# Sheet1.net
KiCad netlist of a schematic drawn in Altium Designer
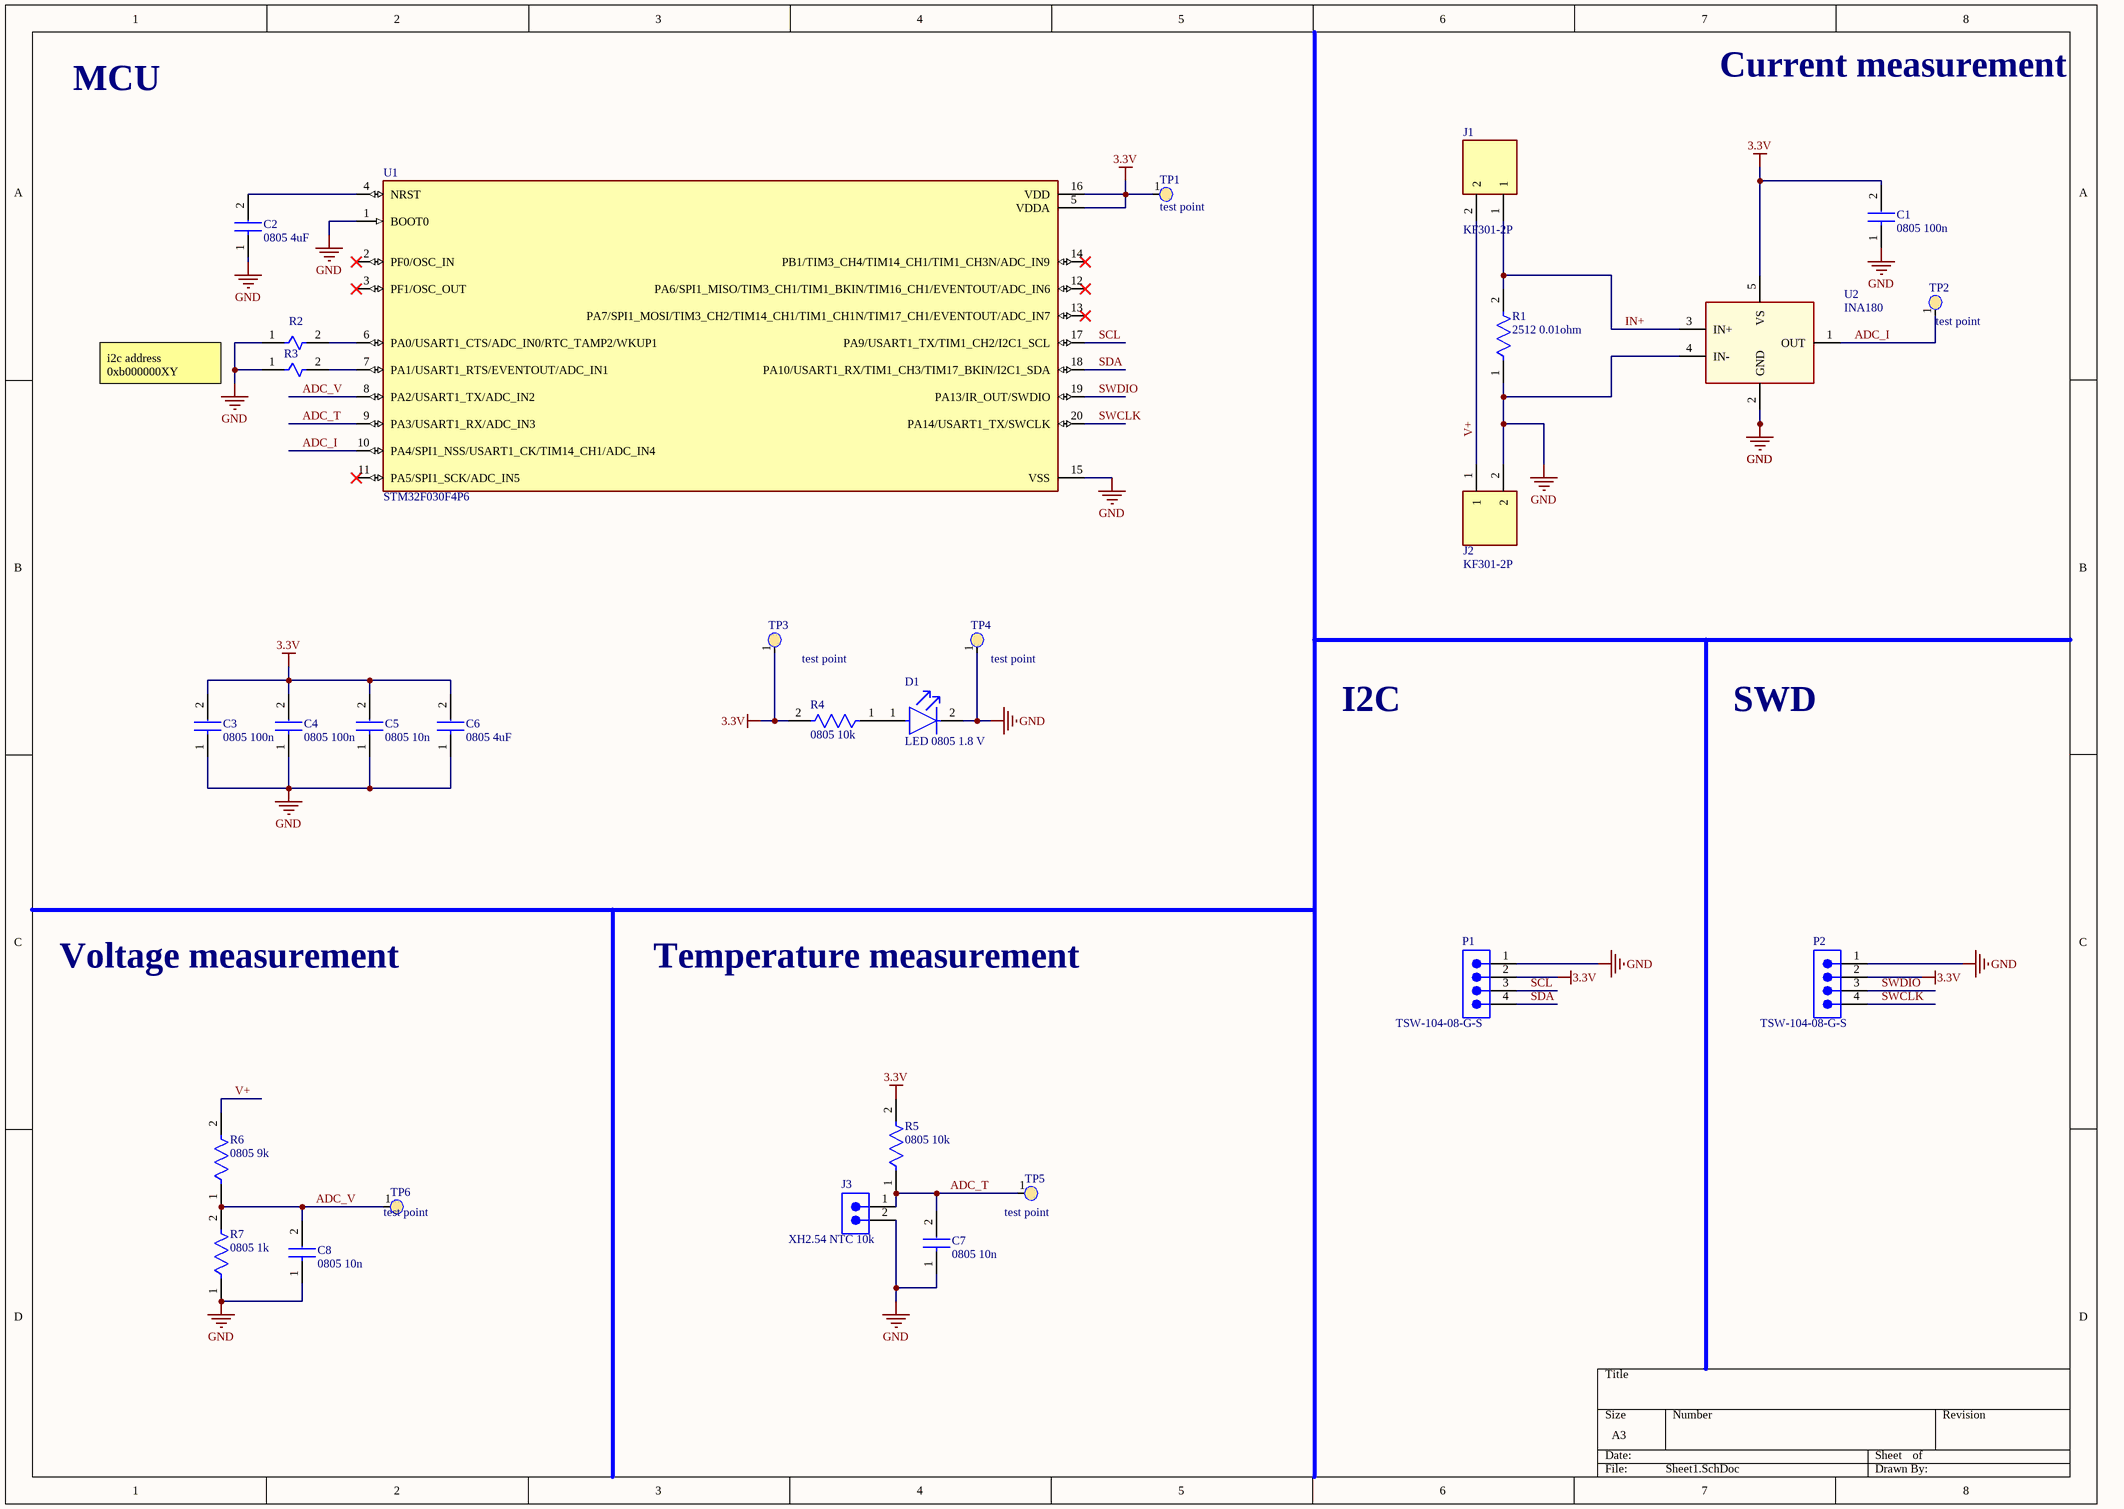
[diagram p0: Sheet1.SchDoc]

(export (version "E")
  (design (tool "Eeschema 10.0.6"))
  (components
    (comp (ref "C1")
      (value "0805 100n")
      (footprint "CAP 0805 IPC_A")
      (description "Chip Multilayer Ceramic Capacitors for General Purpose, 0805, 2200pF, C0G, 30ppm/°C, 5%, 250V")
      (fields (field (name "TOLERANCE") "5%"))
      (libsource (lib "Schlib1") (part "CAP"))
    )
    (comp (ref "C2")
      (value "0805 4uF")
      (footprint "CAP 0805 IPC_A")
      (description "Chip Multilayer Ceramic Capacitors for General Purpose, 0805, 2200pF, C0G, 30ppm/°C, 5%, 250V")
      (fields (field (name "TOLERANCE") "5%"))
      (libsource (lib "Schlib1") (part "CAP"))
    )
    (comp (ref "C3")
      (value "0805 100n")
      (footprint "CAP 0805 IPC_A")
      (description "Chip Multilayer Ceramic Capacitors for General Purpose, 0805, 2200pF, C0G, 30ppm/°C, 5%, 250V")
      (fields (field (name "TOLERANCE") "5%"))
      (libsource (lib "Schlib1") (part "CAP"))
    )
    (comp (ref "C4")
      (value "0805 100n")
      (footprint "CAP 0805 IPC_A")
      (description "Chip Multilayer Ceramic Capacitors for General Purpose, 0805, 2200pF, C0G, 30ppm/°C, 5%, 250V")
      (fields (field (name "TOLERANCE") "5%"))
      (libsource (lib "Schlib1") (part "CAP"))
    )
    (comp (ref "C5")
      (value "0805 10n")
      (footprint "CAP 0805 IPC_A")
      (description "Chip Multilayer Ceramic Capacitors for General Purpose, 0805, 2200pF, C0G, 30ppm/°C, 5%, 250V")
      (fields (field (name "TOLERANCE") "5%"))
      (libsource (lib "Schlib1") (part "CAP"))
    )
    (comp (ref "C6")
      (value "0805 4uF")
      (footprint "CAP 0805 IPC_A")
      (description "Chip Multilayer Ceramic Capacitors for General Purpose, 0805, 2200pF, C0G, 30ppm/°C, 5%, 250V")
      (fields (field (name "TOLERANCE") "5%"))
      (libsource (lib "Schlib1") (part "CAP"))
    )
    (comp (ref "C7")
      (value "0805 10n")
      (footprint "CAP 0805 IPC_A")
      (description "Chip Multilayer Ceramic Capacitors for General Purpose, 0805, 2200pF, C0G, 30ppm/°C, 5%, 250V")
      (fields (field (name "TOLERANCE") "5%"))
      (libsource (lib "Schlib1") (part "CAP"))
    )
    (comp (ref "C8")
      (value "0805 10n")
      (footprint "CAP 0805 IPC_A")
      (description "Chip Multilayer Ceramic Capacitors for General Purpose, 0805, 2200pF, C0G, 30ppm/°C, 5%, 250V")
      (fields (field (name "TOLERANCE") "5%"))
      (libsource (lib "Schlib1") (part "CAP"))
    )
    (comp (ref "D1")
      (value "LED 0805 1.8 V")
      (footprint "LED-0805- MFG")
      (description "LED BLUE CLEAR 0805 SMD")
      (libsource (lib "Schlib1") (part "led 0805"))
    )
    (comp (ref "J1")
      (value "KF301-2P")
      (footprint "KF301")
      (description "2 Pin Terminal Block 5mm Pitch")
      (fields (field (name "MF") "Handson Technology"))
      (libsource (lib "") (part "KF301-2P_1"))
    )
    (comp (ref "J2")
      (value "KF301-2P")
      (footprint "KF301")
      (description "2 Pin Terminal Block 5mm Pitch")
      (fields (field (name "MF") "Handson Technology"))
      (libsource (lib "Schlib1") (part "KF301-2P"))
    )
    (comp (ref "J3")
      (value "XH2.54 NTC 10k")
      (footprint "B2B-XH-A_LF_SN-MFG")
      (description "CONN HEADER VERT 2POS 2.5MM")
      (libsource (lib "Schlib1") (part "XH2.54 2 pin"))
    )
    (comp (ref "P1")
      (value "TSW-104-08-G-S")
      (footprint "header4pin")
      (description "0.025\" SQ Post Header, Through-hole, Vertical, -55 to 125 degC, 2.54 mm Pitch, 4-Pin, Male, RoHS")
      (fields (field (name "MANUFACTURER") "Samtec"))
      (libsource (lib "Schlib1") (part "header4pin"))
    )
    (comp (ref "P2")
      (value "TSW-104-08-G-S")
      (footprint "header4pin")
      (description "0.025\" SQ Post Header, Through-hole, Vertical, -55 to 125 degC, 2.54 mm Pitch, 4-Pin, Male, RoHS")
      (fields (field (name "MANUFACTURER") "Samtec"))
      (libsource (lib "Schlib1") (part "header4pin"))
    )
    (comp (ref "R1")
      (value "2512 0.01ohm")
      (footprint "R 2512 A")
      (libsource (lib "Schlib1") (part "R 2512"))
    )
    (comp (ref "R2") (value "0603") (footprint "0603-IPC_C") (libsource (lib "Schlib1") (part "0603")))
    (comp (ref "R3") (value "0603") (footprint "0603-IPC_C") (libsource (lib "Schlib1") (part "0603")))
    (comp (ref "R4") (value "0805 10k") (footprint "R 0805 A") (libsource (lib "Schlib1") (part "R 0805")))
    (comp (ref "R5") (value "0805 10k") (footprint "R 0805 A") (libsource (lib "Schlib1") (part "R 0805")))
    (comp (ref "R6") (value "0805 9k") (footprint "R 0805 A") (libsource (lib "Schlib1") (part "R 0805")))
    (comp (ref "R7") (value "0805 1k") (footprint "R 0805 A") (libsource (lib "Schlib1") (part "R 0805")))
    (comp (ref "TP1")
      (value "test point")
      (footprint "testpoint")
      (libsource (lib "Schlib1") (part "testpoint"))
    )
    (comp (ref "TP2")
      (value "test point")
      (footprint "testpoint")
      (libsource (lib "Schlib1") (part "testpoint"))
    )
    (comp (ref "TP3")
      (value "test point")
      (footprint "testpoint")
      (libsource (lib "Schlib1") (part "testpoint"))
    )
    (comp (ref "TP4")
      (value "test point")
      (footprint "testpoint")
      (libsource (lib "Schlib1") (part "testpoint"))
    )
    (comp (ref "TP5")
      (value "test point")
      (footprint "testpoint")
      (libsource (lib "Schlib1") (part "testpoint"))
    )
    (comp (ref "TP6")
      (value "test point")
      (footprint "testpoint")
      (libsource (lib "Schlib1") (part "testpoint"))
    )
    (comp (ref "U1")
      (value "STM32F030F4P6")
      (footprint "STM32F030 - 20pin")
      (description "ARMÂ® CortexÂ®-M0 STM32F0 Microcontroller IC 32-Bit Single-Core 48MHz 16KB (16K x 8) FLASH")
      (fields (field (name "MF") "STMicroelectronics"))
      (libsource (lib "Schlib1") (part "STM32F030F4P6"))
    )
    (comp (ref "U2")
      (value "INA180")
      (footprint "INA180")
      (description "26V, 350kHz current sense amplifier")
      (fields (field (name "MF") "Texas Instruments") (field (name "MP") "INA180B1IDBVT"))
      (libsource (lib "Schlib1") (part "INA180"))
    )
  )
  (nets
    (net (code "1") (name "/ADC_I") (class "Default")
      (node (ref "TP2") (pin "1") (pinfunction "testpoint_1") (pintype "passive"))
      (node (ref "U1") (pin "10") (pinfunction "PA4/SPI1_NSS/USART1_CK/TIM14_CH1/ADC_IN4_10") (pintype "bidirectional"))
      (node (ref "U2") (pin "1") (pinfunction "OUT_1") (pintype "passive"))
    )
    (net (code "2") (name "/ADC_T") (class "Default")
      (node (ref "C7") (pin "2") (pinfunction "2_2") (pintype "passive"))
      (node (ref "J3") (pin "1") (pinfunction "1_1") (pintype "passive"))
      (node (ref "R5") (pin "1") (pinfunction "1_1") (pintype "passive"))
      (node (ref "TP5") (pin "1") (pinfunction "testpoint_1") (pintype "passive"))
      (node (ref "U1") (pin "9") (pinfunction "PA3/USART1_RX/ADC_IN3_9") (pintype "bidirectional"))
    )
    (net (code "3") (name "/ADC_V") (class "Default")
      (node (ref "C8") (pin "2") (pinfunction "2_2") (pintype "passive"))
      (node (ref "R6") (pin "1") (pinfunction "1_1") (pintype "passive"))
      (node (ref "R7") (pin "2") (pinfunction "2_2") (pintype "passive"))
      (node (ref "TP6") (pin "1") (pinfunction "testpoint_1") (pintype "passive"))
      (node (ref "U1") (pin "8") (pinfunction "PA2/USART1_TX/ADC_IN2_8") (pintype "bidirectional"))
    )
    (net (code "4") (name "/IN+") (class "Default")
      (node (ref "J1") (pin "1") (pinfunction "1_1") (pintype "passive"))
      (node (ref "R1") (pin "2") (pinfunction "2_2") (pintype "passive"))
      (node (ref "U2") (pin "3") (pinfunction "IN+_3") (pintype "passive"))
    )
    (net (code "5") (name "/SCL") (class "Default")
      (node (ref "P1") (pin "3") (pinfunction "3_3") (pintype "passive"))
      (node (ref "U1") (pin "17") (pinfunction "PA9/USART1_TX/TIM1_CH2/I2C1_SCL_17") (pintype "bidirectional"))
    )
    (net (code "6") (name "/SDA") (class "Default")
      (node (ref "P1") (pin "4") (pinfunction "4_4") (pintype "passive"))
      (node (ref "U1") (pin "18") (pinfunction "PA10/USART1_RX/TIM1_CH3/TIM17_BKIN/I2C1_SDA_18") (pintype "bidirectional"))
    )
    (net (code "7") (name "/SWCLK") (class "Default")
      (node (ref "P2") (pin "4") (pinfunction "4_4") (pintype "passive"))
      (node (ref "U1") (pin "20") (pinfunction "PA14/USART1_TX/SWCLK_20") (pintype "bidirectional"))
    )
    (net (code "8") (name "/SWDIO") (class "Default")
      (node (ref "P2") (pin "3") (pinfunction "3_3") (pintype "passive"))
      (node (ref "U1") (pin "19") (pinfunction "PA13/IR_OUT/SWDIO_19") (pintype "bidirectional"))
    )
    (net (code "9") (name "/V+") (class "Default")
      (node (ref "J1") (pin "2") (pinfunction "2_2") (pintype "passive"))
      (node (ref "J2") (pin "1") (pinfunction "1_1") (pintype "passive"))
      (node (ref "R6") (pin "2") (pinfunction "2_2") (pintype "passive"))
    )
    (net (code "10") (name "3.3V") (class "Default")
      (node (ref "C1") (pin "2") (pinfunction "2_2") (pintype "passive"))
      (node (ref "C3") (pin "2") (pinfunction "2_2") (pintype "passive"))
      (node (ref "C4") (pin "2") (pinfunction "2_2") (pintype "passive"))
      (node (ref "C5") (pin "2") (pinfunction "2_2") (pintype "passive"))
      (node (ref "C6") (pin "2") (pinfunction "2_2") (pintype "passive"))
      (node (ref "P1") (pin "2") (pinfunction "2_2") (pintype "passive"))
      (node (ref "P2") (pin "2") (pinfunction "2_2") (pintype "passive"))
      (node (ref "R4") (pin "2") (pinfunction "2_2") (pintype "passive"))
      (node (ref "R5") (pin "2") (pinfunction "2_2") (pintype "passive"))
      (node (ref "TP1") (pin "1") (pinfunction "testpoint_1") (pintype "passive"))
      (node (ref "TP3") (pin "1") (pinfunction "testpoint_1") (pintype "passive"))
      (node (ref "U1") (pin "16") (pinfunction "VDD_16") (pintype "power_in"))
      (node (ref "U1") (pin "5") (pinfunction "VDDA_5") (pintype "power_in"))
      (node (ref "U2") (pin "5") (pinfunction "VS_5") (pintype "power_in"))
    )
    (net (code "11") (name "GND") (class "Default")
      (node (ref "C1") (pin "1") (pinfunction "1_1") (pintype "passive"))
      (node (ref "C2") (pin "1") (pinfunction "1_1") (pintype "passive"))
      (node (ref "C3") (pin "1") (pinfunction "1_1") (pintype "passive"))
      (node (ref "C4") (pin "1") (pinfunction "1_1") (pintype "passive"))
      (node (ref "C5") (pin "1") (pinfunction "1_1") (pintype "passive"))
      (node (ref "C6") (pin "1") (pinfunction "1_1") (pintype "passive"))
      (node (ref "C7") (pin "1") (pinfunction "1_1") (pintype "passive"))
      (node (ref "C8") (pin "1") (pinfunction "1_1") (pintype "passive"))
      (node (ref "D1") (pin "2") (pinfunction "C_2") (pintype "passive"))
      (node (ref "J2") (pin "2") (pinfunction "2_2") (pintype "passive"))
      (node (ref "J3") (pin "2") (pinfunction "2_2") (pintype "passive"))
      (node (ref "P1") (pin "1") (pinfunction "1_1") (pintype "passive"))
      (node (ref "P2") (pin "1") (pinfunction "1_1") (pintype "passive"))
      (node (ref "R1") (pin "1") (pinfunction "1_1") (pintype "passive"))
      (node (ref "R2") (pin "1") (pinfunction "1_1") (pintype "passive"))
      (node (ref "R3") (pin "1") (pinfunction "1_1") (pintype "passive"))
      (node (ref "R7") (pin "1") (pinfunction "1_1") (pintype "passive"))
      (node (ref "TP4") (pin "1") (pinfunction "testpoint_1") (pintype "passive"))
      (node (ref "U1") (pin "1") (pinfunction "BOOT0_1") (pintype "input"))
      (node (ref "U1") (pin "15") (pinfunction "VSS_15") (pintype "power_in"))
      (node (ref "U2") (pin "2") (pinfunction "GND_2") (pintype "power_in"))
      (node (ref "U2") (pin "4") (pinfunction "IN-_4") (pintype "passive"))
    )
    (net (code "12") (name "Net-(D1-A)") (class "Default")
      (node (ref "D1") (pin "1") (pinfunction "A_1") (pintype "passive"))
      (node (ref "R4") (pin "1") (pinfunction "1_1") (pintype "passive"))
    )
    (net (code "13") (name "Net-(U1-NRST)") (class "Default")
      (node (ref "C2") (pin "2") (pinfunction "2_2") (pintype "passive"))
      (node (ref "U1") (pin "4") (pinfunction "NRST_4") (pintype "bidirectional"))
    )
    (net (code "14") (name "Net-(U1-PA0{slash}USART1_CTS{slash}ADC_IN0{slash}RTC_TAMP2{slash}WKUP1)") (class "Default")
      (node (ref "R2") (pin "2") (pinfunction "2_2") (pintype "passive"))
      (node (ref "U1") (pin "6") (pinfunction "PA0/USART1_CTS/ADC_IN0/RTC_TAMP2/WKUP1_6") (pintype "bidirectional"))
    )
    (net (code "15") (name "Net-(U1-PA1{slash}USART1_RTS{slash}EVENTOUT{slash}ADC_IN1)") (class "Default")
      (node (ref "R3") (pin "2") (pinfunction "2_2") (pintype "passive"))
      (node (ref "U1") (pin "7") (pinfunction "PA1/USART1_RTS/EVENTOUT/ADC_IN1_7") (pintype "bidirectional"))
    )
    (net (code "16") (name "unconnected-(U1-PA5{slash}SPI1_SCK{slash}ADC_IN5-Pad11)") (class "Default")
      (node (ref "U1") (pin "11") (pinfunction "PA5/SPI1_SCK/ADC_IN5_11") (pintype "bidirectional+no_connect"))
    )
    (net (code "17") (name "unconnected-(U1-PA6{slash}SPI1_MISO{slash}TIM3_CH1{slash}TIM1_BKIN{slash}TIM16_CH1{slash}EVENTOUT{slash}ADC_IN6-Pad12)") (class "Default")
      (node (ref "U1") (pin "12") (pinfunction "PA6/SPI1_MISO/TIM3_CH1/TIM1_BKIN/TIM16_CH1/EVENTOUT/ADC_IN6_12") (pintype "bidirectional+no_connect"))
    )
    (net (code "18") (name "unconnected-(U1-PA7{slash}SPI1_MOSI{slash}TIM3_CH2{slash}TIM14_CH1{slash}TIM1_CH1N{slash}TIM17_CH1{slash}EVENTOUT{slash}ADC_IN7-Pad13)") (class "Default")
      (node (ref "U1") (pin "13") (pinfunction "PA7/SPI1_MOSI/TIM3_CH2/TIM14_CH1/TIM1_CH1N/TIM17_CH1/EVENTOUT/ADC_IN7_13") (pintype "bidirectional+no_connect"))
    )
    (net (code "19") (name "unconnected-(U1-PB1{slash}TIM3_CH4{slash}TIM14_CH1{slash}TIM1_CH3N{slash}ADC_IN9-Pad14)") (class "Default")
      (node (ref "U1") (pin "14") (pinfunction "PB1/TIM3_CH4/TIM14_CH1/TIM1_CH3N/ADC_IN9_14") (pintype "bidirectional+no_connect"))
    )
    (net (code "20") (name "unconnected-(U1-PF0{slash}OSC_IN-Pad2)") (class "Default")
      (node (ref "U1") (pin "2") (pinfunction "PF0/OSC_IN_2") (pintype "bidirectional+no_connect"))
    )
    (net (code "21") (name "unconnected-(U1-PF1{slash}OSC_OUT-Pad3)") (class "Default")
      (node (ref "U1") (pin "3") (pinfunction "PF1/OSC_OUT_3") (pintype "bidirectional+no_connect"))
    )
  )
)
